# 3V-Switcher-50mA.net
KiCad netlist of a schematic drawn in Altium Designer
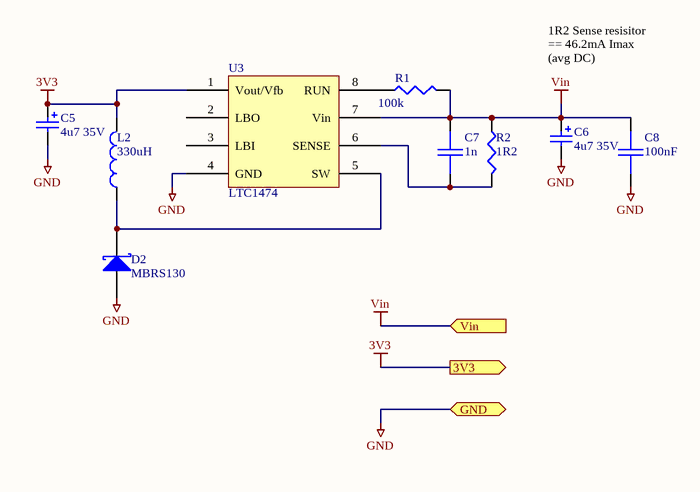
[diagram p0: 3V-Switcher-50mA.SCHDOC]

(export (version "E")
  (design (tool "Eeschema 10.0.6"))
  (components
    (comp (ref "C5")
      (value "4u7 35V")
      (footprint "MCCT-CASEC")
      (description "Polarized Capacitor (Surface Mount)")
      (libsource (lib "Miscellaneous Devices") (part "Cap Pol3"))
    )
    (comp (ref "C6")
      (value "4u7 35V")
      (footprint "MCCT-CASEC")
      (description "Polarized Capacitor (Surface Mount)")
      (libsource (lib "Miscellaneous Devices") (part "Cap Pol3"))
    )
    (comp (ref "C7")
      (value "1n")
      (footprint "0603")
      (description "Capacitor")
      (libsource (lib "Miscellaneous Devices") (part "CAP"))
    )
    (comp (ref "C8")
      (value "100nF")
      (footprint "0603")
      (description "Capacitor")
      (libsource (lib "Miscellaneous Devices") (part "CAP"))
    )
    (comp (ref "D2")
      (value "MBRS130")
      (footprint "SMB")
      (description "Schottky Diode")
      (libsource (lib "RCLDQ") (part "D SCHOTTKY"))
    )
    (comp (ref "L2")
      (value "330uH")
      (footprint "1812")
      (description "Inductor")
      (libsource (lib "Miscellaneous Devices") (part "Inductor"))
    )
    (comp (ref "R1")
      (value "100k")
      (footprint "0603")
      (description "Resistor")
      (libsource (lib "RCLDQ") (part "RES1"))
    )
    (comp (ref "R2")
      (value "1R2")
      (footprint "0603")
      (description "Resistor")
      (libsource (lib "Miscellaneous Devices") (part "RES1"))
    )
    (comp (ref "U3")
      (value "LTC1474")
      (footprint "SO8")
      (description "Step-down converter")
      (libsource (lib "MiscellaneousIC") (part "LTC1474"))
    )
  )
  (nets
    (net (code "1") (name "3V3") (class "Default")
      (node (ref "C5") (pin "1") (pinfunction "1_1") (pintype "passive"))
      (node (ref "L2") (pin "2") (pinfunction "2_2") (pintype "passive"))
      (node (ref "U3") (pin "1") (pinfunction "Vout/Vfb_1") (pintype "passive"))
    )
    (net (code "2") (name "GND") (class "Default")
      (node (ref "C5") (pin "2") (pinfunction "2_2") (pintype "passive"))
      (node (ref "C6") (pin "2") (pinfunction "2_2") (pintype "passive"))
      (node (ref "C8") (pin "2") (pinfunction "2_2") (pintype "passive"))
      (node (ref "D2") (pin "A") (pinfunction "A_A") (pintype "passive"))
      (node (ref "U3") (pin "4") (pinfunction "GND_4") (pintype "passive"))
    )
    (net (code "3") (name "Net-(U3-RUN)") (class "Default")
      (node (ref "R1") (pin "1") (pinfunction "1_1") (pintype "passive"))
      (node (ref "U3") (pin "8") (pinfunction "RUN_8") (pintype "passive"))
    )
    (net (code "4") (name "Net-(U3-SENSE)") (class "Default")
      (node (ref "C7") (pin "2") (pinfunction "2_2") (pintype "passive"))
      (node (ref "R2") (pin "2") (pinfunction "2_2") (pintype "passive"))
      (node (ref "U3") (pin "6") (pinfunction "SENSE_6") (pintype "passive"))
    )
    (net (code "5") (name "Net-(U3-SW)") (class "Default")
      (node (ref "D2") (pin "K") (pinfunction "K_K") (pintype "passive"))
      (node (ref "L2") (pin "1") (pinfunction "1_1") (pintype "passive"))
      (node (ref "U3") (pin "5") (pinfunction "SW_5") (pintype "passive"))
    )
    (net (code "6") (name "Vin") (class "Default")
      (node (ref "C6") (pin "1") (pinfunction "1_1") (pintype "passive"))
      (node (ref "C7") (pin "1") (pinfunction "1_1") (pintype "passive"))
      (node (ref "C8") (pin "1") (pinfunction "1_1") (pintype "passive"))
      (node (ref "R1") (pin "2") (pinfunction "2_2") (pintype "passive"))
      (node (ref "R2") (pin "1") (pinfunction "1_1") (pintype "passive"))
      (node (ref "U3") (pin "7") (pinfunction "Vin_7") (pintype "passive"))
    )
    (net (code "7") (name "unconnected-(U3-LBI-Pad3)") (class "Default")
      (node (ref "U3") (pin "3") (pinfunction "LBI_3") (pintype "passive"))
    )
    (net (code "8") (name "unconnected-(U3-LBO-Pad2)") (class "Default")
      (node (ref "U3") (pin "2") (pinfunction "LBO_2") (pintype "passive"))
    )
  )
)
